# Percep_o_T_rmica.net
KiCad netlist of a schematic drawn in EasyEDA
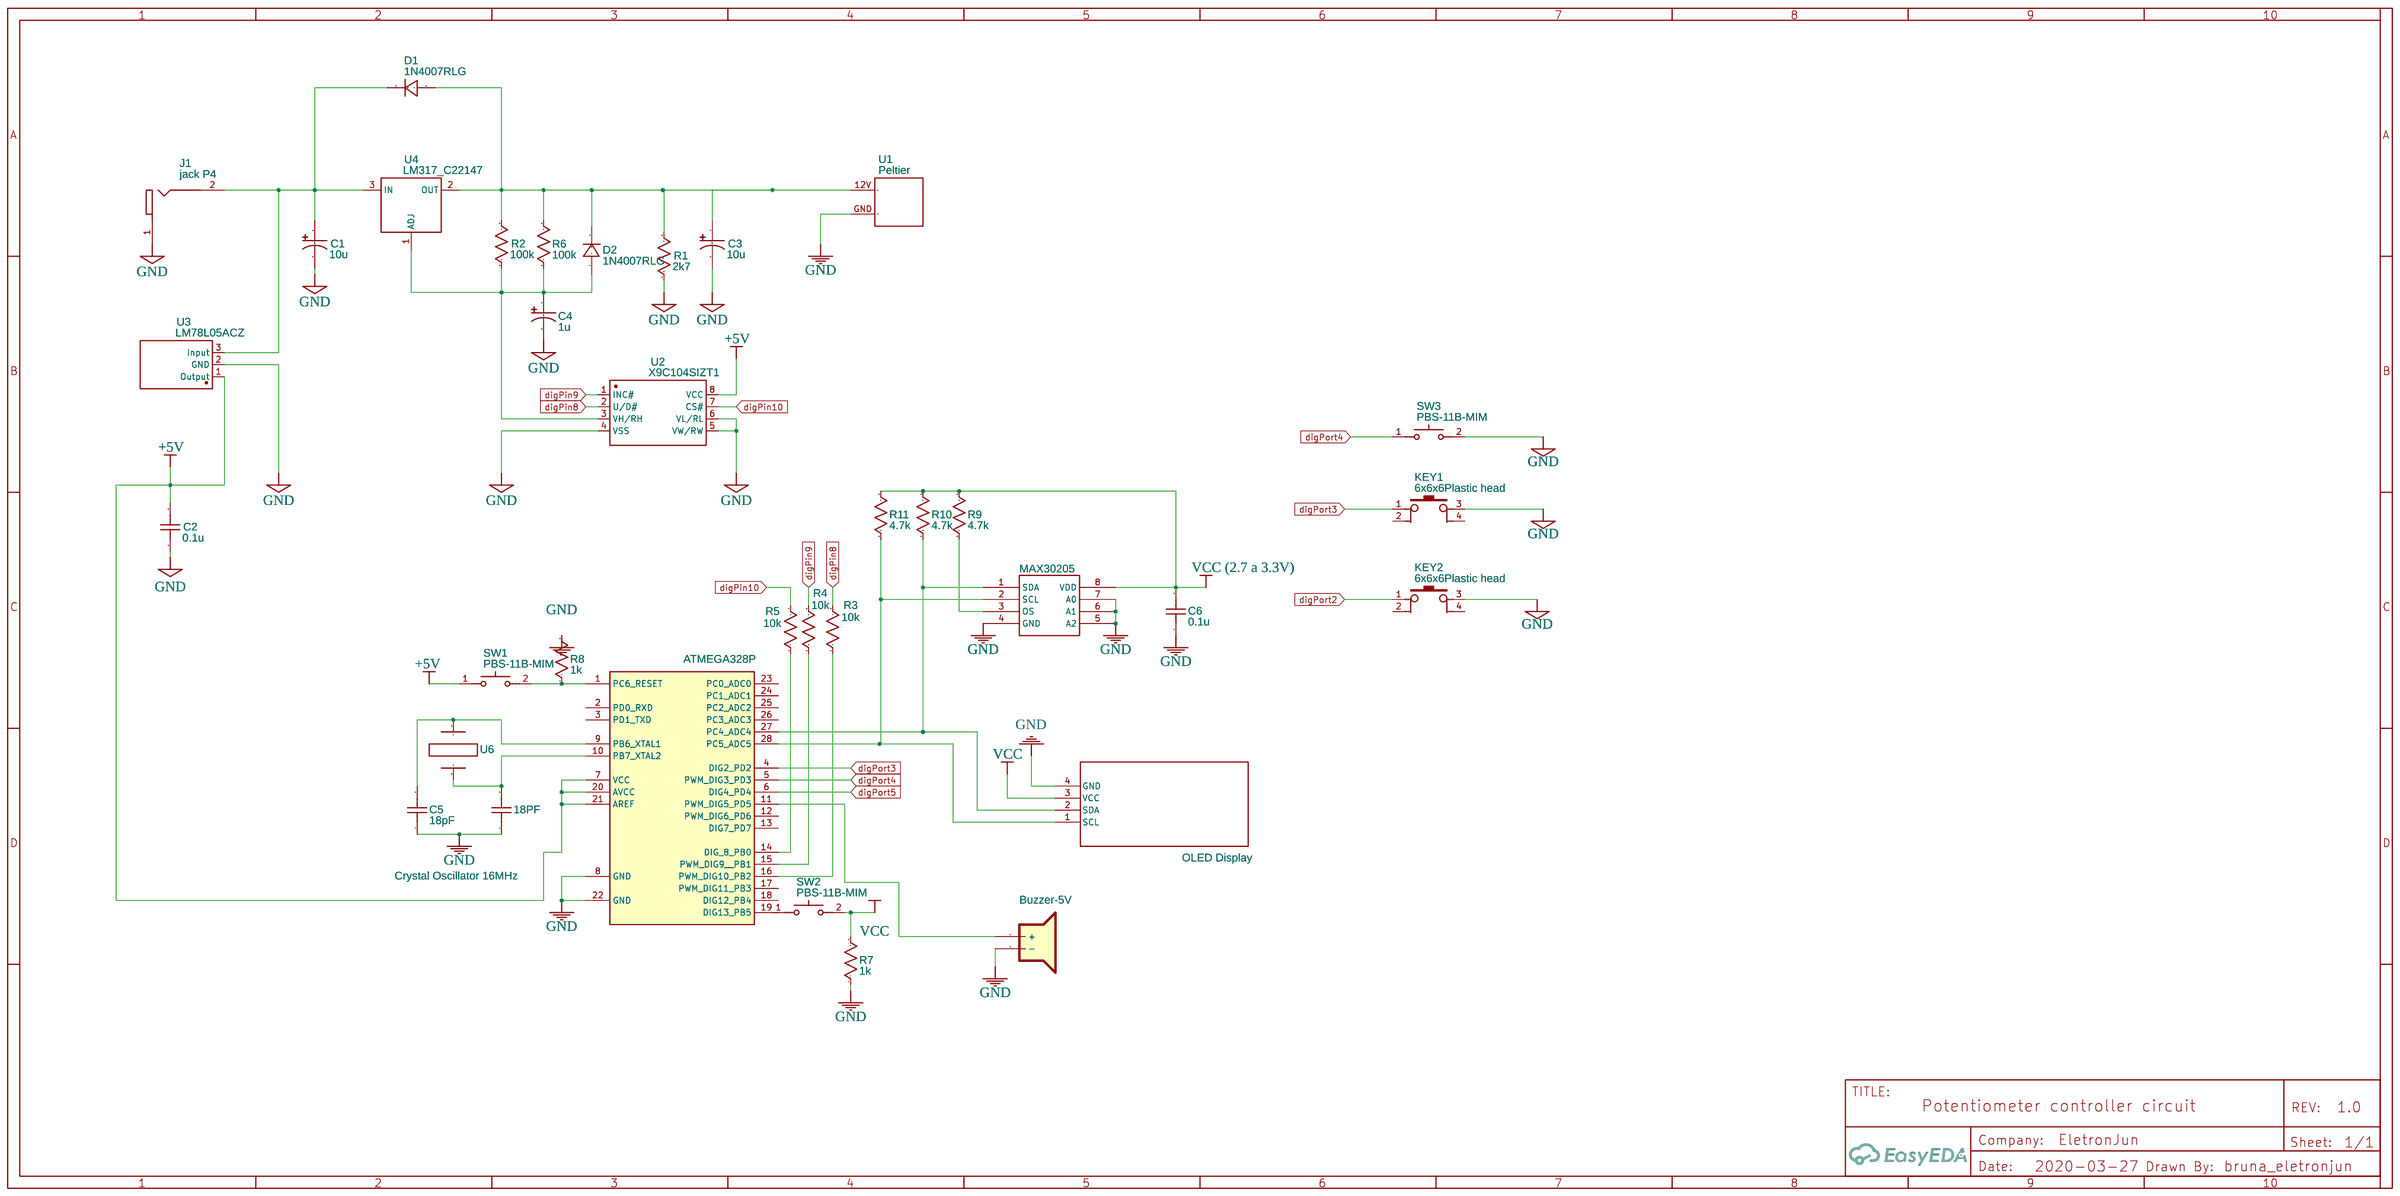
[diagram p0: schematic sheet]

(export (version "E")
  (design (tool "Eeschema 10.0.6"))
  (components
    (comp (ref "18PF") (value "1u") (libsource (lib "") (part "Cap_RAD-0.1_US_1")))
    (comp (ref "BZ1")
      (value "Buzzer-5V")
      (fields (field (name "BOM_Manufacturer Part") "M12G3") (field (name "BOM_Supplier Part") "0237-0021-7"))
      (libsource (lib "") (part "Unknown_850_-35"))
    )
    (comp (ref "C1") (value "10u") (libsource (lib "") (part "Cap_Electrolytic(TH)_D3.0XF1.5_US")))
    (comp (ref "C2") (value "0.1u") (libsource (lib "") (part "Cap_RAD-0.1_US")))
    (comp (ref "C3") (value "10u") (libsource (lib "") (part "Cap_Electrolytic(TH)_D3.0XF1.5_US_1")))
    (comp (ref "C4") (value "1u") (libsource (lib "") (part "Cap_Electrolytic(TH)_D3.0XF1.5_US_1")))
    (comp (ref "C5") (value "18pF") (libsource (lib "") (part "Cap_RAD-0.1_US")))
    (comp (ref "C6") (value "0.1u") (libsource (lib "") (part "Cap_RAD-0.1_US")))
    (comp (ref "D1")
      (value "1N4007RLG")
      (fields (field (name "BOM_Supplier Part") "C53568"))
      (libsource (lib "") (part "1N4007RLG_1"))
    )
    (comp (ref "D2")
      (value "1N4007RLG")
      (fields (field (name "BOM_Supplier Part") "C53568"))
      (libsource (lib "") (part "1N4007RLG"))
    )
    (comp (ref "J1")
      (value "jack P4")
      (fields
        (field (name "BOM_Manufacturer Part") "RAPC722X")
        (field (name "BOM_Supplier Part") "502-RAPC722X")
      )
      (libsource (lib "") (part "jack P4"))
    )
    (comp (ref "KEY1")
      (value "6x6x6Plastic head")
      (fields (field (name "BOM_Supplier Part") "C23550"))
      (libsource (lib "") (part "6x6x6Plastic head"))
    )
    (comp (ref "KEY2")
      (value "6x6x6Plastic head")
      (fields (field (name "BOM_Supplier Part") "C23550"))
      (libsource (lib "") (part "6x6x6Plastic head"))
    )
    (comp (ref "R1") (value "2k7") (libsource (lib "") (part "Res_AXIAL-0.3(1/8W)_US")))
    (comp (ref "R2") (value "100k") (libsource (lib "") (part "Res_AXIAL-0.3(1/8W)_US")))
    (comp (ref "R3") (value "10k") (libsource (lib "") (part "Res_AXIAL-0.3(1/8W)_US")))
    (comp (ref "R4") (value "10k") (libsource (lib "") (part "Res_AXIAL-0.3(1/8W)_US")))
    (comp (ref "R5") (value "10k") (libsource (lib "") (part "Res_AXIAL-0.3(1/8W)_US")))
    (comp (ref "R6") (value "100k") (libsource (lib "") (part "Res_AXIAL-0.3(1/8W)_US")))
    (comp (ref "R7") (value "1k") (libsource (lib "") (part "Res_AXIAL-0.3(1/8W)_US")))
    (comp (ref "R8") (value "1k") (libsource (lib "") (part "Res_AXIAL-0.3(1/8W)_US")))
    (comp (ref "R9") (value "4.7k") (libsource (lib "") (part "Res_AXIAL-0.3(1/8W)_US")))
    (comp (ref "R10") (value "4.7k") (libsource (lib "") (part "Res_AXIAL-0.3(1/8W)_US")))
    (comp (ref "R11") (value "4.7k") (libsource (lib "") (part "Res_AXIAL-0.3(1/8W)_US")))
    (comp (ref "SW1")
      (value "PBS-11B-MIM")
      (fields
        (field (name "BOM_Manufacturer Part") "SKRKAHE020")
        (field (name "BOM_Supplier Part") "C202388")
      )
      (libsource (lib "") (part "Unknown_405_-245"))
    )
    (comp (ref "SW2")
      (value "PBS-11B-MIM")
      (fields
        (field (name "BOM_Manufacturer Part") "SKRKAHE020")
        (field (name "BOM_Supplier Part") "C202388")
      )
      (libsource (lib "") (part "Unknown_665_-55"))
    )
    (comp (ref "SW3")
      (value "PBS-11B-MIM")
      (fields
        (field (name "BOM_Manufacturer Part") "SKRKAHE020")
        (field (name "BOM_Supplier Part") "C202388")
      )
      (libsource (lib "") (part "Unknown_1180_-450"))
    )
    (comp (ref "U1") (value "Peltier") (libsource (lib "") (part "Peltier")))
    (comp (ref "U2")
      (value "X9C104SIZT1")
      (fields (field (name "BOM_Supplier Part") "C11979"))
      (libsource (lib "") (part "X9C104SIZT1"))
    )
    (comp (ref "U3")
      (value "LM78L05ACZ")
      (fields (field (name "BOM_Supplier Part") "C112082"))
      (libsource (lib "") (part "LM78L05ACZ"))
    )
    (comp (ref "U4")
      (value "LM317_C22147")
      (fields (field (name "BOM_Manufacturer Part") "LM317") (field (name "BOM_Supplier Part") "C22147"))
      (libsource (lib "") (part "LM317_C22147"))
    )
    (comp (ref "U6") (value "Crystal Oscillator 16MHz") (libsource (lib "") (part "Unknown_370_-195")))
    (comp (ref "U7")
      (value "ATMEGA328P")
      (fields
        (field (name "BOM_Manufacturer Part") "ATMEGA328P-PU")
        (field (name "BOM_Supplier Part") "C33901")
      )
      (libsource (lib "") (part "Unknown_540_-125"))
    )
    (comp (ref "U8") (value "MAX30205") (libsource (lib "") (part "Unknown_865_-310")))
    (comp (ref "U9")
      (value "OLED Display")
      (fields (field (name "BOM_Supplier Part") "undefined"))
      (libsource (lib "") (part "Unknown_950_-145"))
    )
  )
  (nets
    (net (code "1") (name "+5V") (class "Default")
      (node (ref "C2") (pin "2") (pinfunction "2_2") (pintype "unspecified"))
      (node (ref "SW1") (pin "1") (pinfunction "1_1") (pintype "unspecified"))
      (node (ref "U2") (pin "8") (pinfunction "VCC_8") (pintype "unspecified"))
      (node (ref "U3") (pin "1") (pinfunction "Output_1") (pintype "unspecified"))
      (node (ref "U7") (pin "20") (pinfunction "AVCC_20") (pintype "passive"))
      (node (ref "U7") (pin "21") (pinfunction "AREF_21") (pintype "passive"))
      (node (ref "U7") (pin "7") (pinfunction "VCC_7") (pintype "passive"))
    )
    (net (code "2") (name "GND") (class "Default")
      (node (ref "18PF") (pin "1") (pinfunction "1_1") (pintype "unspecified"))
      (node (ref "BZ1") (pin "2") (pinfunction "-_2") (pintype "unspecified"))
      (node (ref "C1") (pin "2") (pinfunction "2_2") (pintype "unspecified"))
      (node (ref "C2") (pin "1") (pinfunction "1_1") (pintype "unspecified"))
      (node (ref "C3") (pin "2") (pinfunction "2_2") (pintype "unspecified"))
      (node (ref "C4") (pin "2") (pinfunction "2_2") (pintype "unspecified"))
      (node (ref "C5") (pin "1") (pinfunction "1_1") (pintype "unspecified"))
      (node (ref "C6") (pin "1") (pinfunction "1_1") (pintype "unspecified"))
      (node (ref "J1") (pin "1") (pinfunction "1_1") (pintype "unspecified"))
      (node (ref "KEY1") (pin "3") (pinfunction "3_3") (pintype "input"))
      (node (ref "KEY2") (pin "3") (pinfunction "3_3") (pintype "input"))
      (node (ref "R1") (pin "1") (pinfunction "1_1") (pintype "unspecified"))
      (node (ref "R7") (pin "1") (pinfunction "1_1") (pintype "unspecified"))
      (node (ref "R8") (pin "2") (pinfunction "2_2") (pintype "unspecified"))
      (node (ref "SW3") (pin "2") (pinfunction "2_2") (pintype "unspecified"))
      (node (ref "U1") (pin "GND") (pinfunction "1_GND") (pintype "passive"))
      (node (ref "U2") (pin "4") (pinfunction "VSS_4") (pintype "unspecified"))
      (node (ref "U2") (pin "5") (pinfunction "VW/RW_5") (pintype "unspecified"))
      (node (ref "U2") (pin "6") (pinfunction "VL/RL_6") (pintype "unspecified"))
      (node (ref "U3") (pin "2") (pinfunction "GND_2") (pintype "unspecified"))
      (node (ref "U7") (pin "22") (pinfunction "GND_22") (pintype "passive"))
      (node (ref "U7") (pin "8") (pinfunction "GND_8") (pintype "passive"))
      (node (ref "U8") (pin "4") (pinfunction "GND_4") (pintype "output"))
      (node (ref "U8") (pin "5") (pinfunction "A2_5") (pintype "output"))
      (node (ref "U8") (pin "6") (pinfunction "A1_6") (pintype "output"))
      (node (ref "U8") (pin "7") (pinfunction "A0_7") (pintype "output"))
      (node (ref "U9") (pin "4") (pinfunction "GND_4") (pintype "unspecified"))
    )
    (net (code "3") (name "Net-(BZ1-+)") (class "Default")
      (node (ref "BZ1") (pin "1") (pinfunction "+_1") (pintype "unspecified"))
      (node (ref "U7") (pin "11") (pinfunction "PWM_DIG5_PD5_11") (pintype "bidirectional"))
    )
    (net (code "4") (name "Net-(D1-A)") (class "Default")
      (node (ref "C3") (pin "1") (pinfunction "1_1") (pintype "unspecified"))
      (node (ref "D1") (pin "2") (pinfunction "A_2") (pintype "unspecified"))
      (node (ref "D2") (pin "1") (pinfunction "C_1") (pintype "unspecified"))
      (node (ref "R1") (pin "2") (pinfunction "2_2") (pintype "unspecified"))
      (node (ref "R2") (pin "2") (pinfunction "2_2") (pintype "unspecified"))
      (node (ref "R6") (pin "2") (pinfunction "2_2") (pintype "unspecified"))
      (node (ref "U1") (pin "12V") (pinfunction "2_12V") (pintype "passive"))
      (node (ref "U4") (pin "2") (pinfunction "OUT_2") (pintype "unspecified"))
    )
    (net (code "5") (name "Net-(D1-C)") (class "Default")
      (node (ref "C1") (pin "1") (pinfunction "1_1") (pintype "unspecified"))
      (node (ref "D1") (pin "1") (pinfunction "C_1") (pintype "unspecified"))
      (node (ref "J1") (pin "2") (pinfunction "2_2") (pintype "unspecified"))
      (node (ref "U3") (pin "3") (pinfunction "Input_3") (pintype "unspecified"))
      (node (ref "U4") (pin "3") (pinfunction "IN_3") (pintype "input"))
    )
    (net (code "6") (name "Net-(D2-A)") (class "Default")
      (node (ref "C4") (pin "1") (pinfunction "1_1") (pintype "unspecified"))
      (node (ref "D2") (pin "2") (pinfunction "A_2") (pintype "unspecified"))
      (node (ref "R2") (pin "1") (pinfunction "1_1") (pintype "unspecified"))
      (node (ref "R6") (pin "1") (pinfunction "1_1") (pintype "unspecified"))
      (node (ref "U2") (pin "3") (pinfunction "VH/RH_3") (pintype "unspecified"))
      (node (ref "U4") (pin "1") (pinfunction "ADJ_1") (pintype "input"))
    )
    (net (code "7") (name "Net-(U7-DIG_8_PB0)") (class "Default")
      (node (ref "R5") (pin "1") (pinfunction "1_1") (pintype "unspecified"))
      (node (ref "U7") (pin "14") (pinfunction "DIG_8_PB0_14") (pintype "bidirectional"))
    )
    (net (code "8") (name "Net-(U7-PB6_XTAL1)") (class "Default")
      (node (ref "C5") (pin "2") (pinfunction "2_2") (pintype "unspecified"))
      (node (ref "U6") (pin "1") (pinfunction "1_1") (pintype "unspecified"))
      (node (ref "U7") (pin "9") (pinfunction "PB6_XTAL1_9") (pintype "bidirectional"))
    )
    (net (code "9") (name "Net-(U7-PB7_XTAL2)") (class "Default")
      (node (ref "18PF") (pin "2") (pinfunction "2_2") (pintype "unspecified"))
      (node (ref "U6") (pin "2") (pinfunction "2_2") (pintype "unspecified"))
      (node (ref "U7") (pin "10") (pinfunction "PB7_XTAL2_10") (pintype "bidirectional"))
    )
    (net (code "10") (name "Net-(U7-PC4_ADC4)") (class "Default")
      (node (ref "R10") (pin "1") (pinfunction "1_1") (pintype "unspecified"))
      (node (ref "U7") (pin "27") (pinfunction "PC4_ADC4_27") (pintype "bidirectional"))
      (node (ref "U8") (pin "1") (pinfunction "SDA_1") (pintype "bidirectional"))
      (node (ref "U9") (pin "2") (pinfunction "SDA_2") (pintype "unspecified"))
    )
    (net (code "11") (name "Net-(U7-PC5_ADC5)") (class "Default")
      (node (ref "R11") (pin "1") (pinfunction "1_1") (pintype "unspecified"))
      (node (ref "U7") (pin "28") (pinfunction "PC5_ADC5_28") (pintype "bidirectional"))
      (node (ref "U8") (pin "2") (pinfunction "SCL_2") (pintype "bidirectional"))
      (node (ref "U9") (pin "1") (pinfunction "SCL_1") (pintype "unspecified"))
    )
    (net (code "12") (name "Net-(U7-PC6_RESET)") (class "Default")
      (node (ref "R8") (pin "1") (pinfunction "1_1") (pintype "unspecified"))
      (node (ref "SW1") (pin "2") (pinfunction "2_2") (pintype "unspecified"))
      (node (ref "U7") (pin "1") (pinfunction "PC6_RESET_1") (pintype "bidirectional"))
    )
    (net (code "13") (name "Net-(U7-PWM_DIG9__PB1)") (class "Default")
      (node (ref "R4") (pin "1") (pinfunction "1_1") (pintype "unspecified"))
      (node (ref "U7") (pin "15") (pinfunction "PWM_DIG9__PB1_15") (pintype "bidirectional"))
    )
    (net (code "14") (name "Net-(U7-PWM_DIG10_PB2)") (class "Default")
      (node (ref "R3") (pin "1") (pinfunction "1_1") (pintype "unspecified"))
      (node (ref "U7") (pin "16") (pinfunction "PWM_DIG10_PB2_16") (pintype "bidirectional"))
    )
    (net (code "15") (name "Net-(U8-OS)") (class "Default")
      (node (ref "R9") (pin "1") (pinfunction "1_1") (pintype "unspecified"))
      (node (ref "U8") (pin "3") (pinfunction "OS_3") (pintype "bidirectional"))
    )
    (net (code "16") (name "VCC") (class "Default")
      (node (ref "R7") (pin "2") (pinfunction "2_2") (pintype "unspecified"))
      (node (ref "SW2") (pin "2") (pinfunction "2_2") (pintype "unspecified"))
      (node (ref "U9") (pin "3") (pinfunction "VCC_3") (pintype "unspecified"))
    )
    (net (code "17") (name "VCC (2.7 a 3.3V)") (class "Default")
      (node (ref "C6") (pin "2") (pinfunction "2_2") (pintype "unspecified"))
      (node (ref "R10") (pin "2") (pinfunction "2_2") (pintype "unspecified"))
      (node (ref "R11") (pin "2") (pinfunction "2_2") (pintype "unspecified"))
      (node (ref "R9") (pin "2") (pinfunction "2_2") (pintype "unspecified"))
      (node (ref "U8") (pin "8") (pinfunction "VDD_8") (pintype "output"))
    )
    (net (code "18") (name "digPin8") (class "Default")
      (node (ref "R3") (pin "2") (pinfunction "2_2") (pintype "unspecified"))
      (node (ref "U2") (pin "2") (pinfunction "U/D#_2") (pintype "unspecified"))
    )
    (net (code "19") (name "digPin9") (class "Default")
      (node (ref "R4") (pin "2") (pinfunction "2_2") (pintype "unspecified"))
      (node (ref "U2") (pin "1") (pinfunction "INC#_1") (pintype "unspecified"))
    )
    (net (code "20") (name "digPin10") (class "Default")
      (node (ref "R5") (pin "2") (pinfunction "2_2") (pintype "unspecified"))
      (node (ref "U2") (pin "7") (pinfunction "CS#_7") (pintype "unspecified"))
    )
    (net (code "21") (name "digPort2") (class "Default")
      (node (ref "KEY2") (pin "1") (pinfunction "1_1") (pintype "input"))
    )
    (net (code "22") (name "digPort3") (class "Default")
      (node (ref "KEY1") (pin "1") (pinfunction "1_1") (pintype "input"))
      (node (ref "U7") (pin "4") (pinfunction "DIG2_PD2_4") (pintype "bidirectional"))
    )
    (net (code "23") (name "digPort4") (class "Default")
      (node (ref "SW3") (pin "1") (pinfunction "1_1") (pintype "unspecified"))
      (node (ref "U7") (pin "5") (pinfunction "PWM_DIG3_PD3_5") (pintype "bidirectional"))
    )
    (net (code "24") (name "digPort5") (class "Default")
      (node (ref "U7") (pin "6") (pinfunction "DIG4_PD4_6") (pintype "bidirectional"))
    )
    (net (code "25") (name "unconnected-(KEY1-Pad2)") (class "Default")
      (node (ref "KEY1") (pin "2") (pinfunction "2_2") (pintype "input"))
    )
    (net (code "26") (name "unconnected-(KEY1-Pad4)") (class "Default")
      (node (ref "KEY1") (pin "4") (pinfunction "4_4") (pintype "input"))
    )
    (net (code "27") (name "unconnected-(KEY2-Pad2)") (class "Default")
      (node (ref "KEY2") (pin "2") (pinfunction "2_2") (pintype "input"))
    )
    (net (code "28") (name "unconnected-(KEY2-Pad4)") (class "Default")
      (node (ref "KEY2") (pin "4") (pinfunction "4_4") (pintype "input"))
    )
    (net (code "29") (name "unconnected-(SW2-Pad1)") (class "Default")
      (node (ref "SW2") (pin "1") (pinfunction "1_1") (pintype "unspecified"))
    )
    (net (code "30") (name "unconnected-(U7-DIG7_PD7-Pad13)") (class "Default")
      (node (ref "U7") (pin "13") (pinfunction "DIG7_PD7_13") (pintype "bidirectional"))
    )
    (net (code "31") (name "unconnected-(U7-DIG12_PB4-Pad18)") (class "Default")
      (node (ref "U7") (pin "18") (pinfunction "DIG12_PB4_18") (pintype "bidirectional"))
    )
    (net (code "32") (name "unconnected-(U7-DIG13_PB5-Pad19)") (class "Default")
      (node (ref "U7") (pin "19") (pinfunction "DIG13_PB5_19") (pintype "bidirectional"))
    )
    (net (code "33") (name "unconnected-(U7-PC0_ADC0-Pad23)") (class "Default")
      (node (ref "U7") (pin "23") (pinfunction "PC0_ADC0_23") (pintype "bidirectional"))
    )
    (net (code "34") (name "unconnected-(U7-PC1_ADC1-Pad24)") (class "Default")
      (node (ref "U7") (pin "24") (pinfunction "PC1_ADC1_24") (pintype "bidirectional"))
    )
    (net (code "35") (name "unconnected-(U7-PC2_ADC2-Pad25)") (class "Default")
      (node (ref "U7") (pin "25") (pinfunction "PC2_ADC2_25") (pintype "bidirectional"))
    )
    (net (code "36") (name "unconnected-(U7-PC3_ADC3-Pad26)") (class "Default")
      (node (ref "U7") (pin "26") (pinfunction "PC3_ADC3_26") (pintype "bidirectional"))
    )
    (net (code "37") (name "unconnected-(U7-PD0_RXD-Pad2)") (class "Default")
      (node (ref "U7") (pin "2") (pinfunction "PD0_RXD_2") (pintype "bidirectional"))
    )
    (net (code "38") (name "unconnected-(U7-PD1_TXD-Pad3)") (class "Default")
      (node (ref "U7") (pin "3") (pinfunction "PD1_TXD_3") (pintype "bidirectional"))
    )
    (net (code "39") (name "unconnected-(U7-PWM_DIG6_PD6-Pad12)") (class "Default")
      (node (ref "U7") (pin "12") (pinfunction "PWM_DIG6_PD6_12") (pintype "bidirectional"))
    )
    (net (code "40") (name "unconnected-(U7-PWM_DIG11_PB3-Pad17)") (class "Default")
      (node (ref "U7") (pin "17") (pinfunction "PWM_DIG11_PB3_17") (pintype "bidirectional"))
    )
  )
)
